# USB_A.net
KiCad netlist of a schematic drawn in Altium Designer
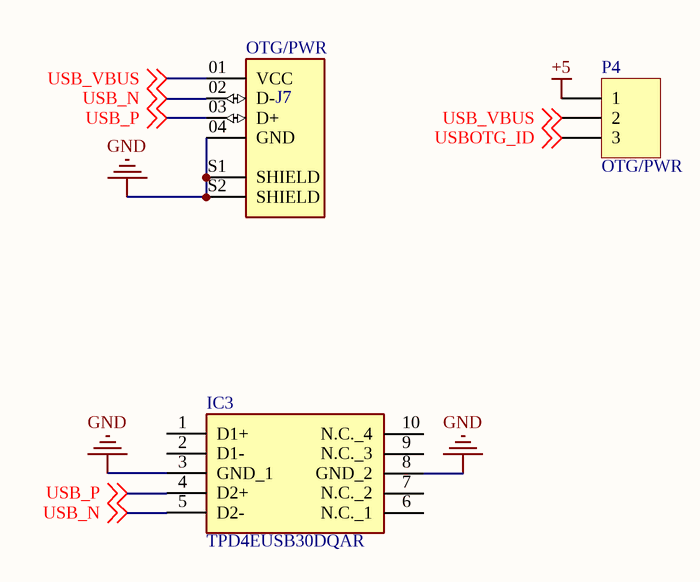
[diagram p0: USB A.SchDoc]

(export (version "E")
  (design (tool "Eeschema 10.0.6"))
  (components
    (comp (ref "IC3")
      (value "TPD4EUSB30DQAR")
      (footprint "SamacSys:DQA(R-PUSON-N10)")
      (description "Integrated Circuit")
      (fields (field (name "MOUSER PART NUMBER") "595-TPD4EUSB30DQAR"))
      (libsource (lib "*") (part "TPD4EUSB30DQAR"))
    )
    (comp (ref "J7")
      (value "OTG/PWR")
      (footprint "SnapEDApcb:SAMTEC_USB-A-S-X-X-SM2")
      (description "USB-A (USB TYPE-A) USB 2.0 Receptacle Connector 4 Position Surface Mount, Right Angle")
      (fields (field (name "MP") "USB-A-S-F-B-SM2") (field (name "MF") "Samtec"))
      (libsource (lib "*") (part "USB-A-S-X-X-SM2"))
    )
    (comp (ref "P4")
      (value "OTG/PWR")
      (footprint "HDR1X3")
      (description "Header, 3-Pin")
      (fields (field (name "PUBLISHER") "Altium Limited"))
      (libsource (lib "Miscellaneous Connectors") (part "Header 3"))
    )
  )
  (nets
    (net (code "1") (name "+5") (class "Default")
      (node (ref "P4") (pin "1") (pinfunction "1_1") (pintype "passive"))
    )
    (net (code "2") (name "GND") (class "Default")
      (node (ref "IC3") (pin "3") (pinfunction "GND_1_3") (pintype "passive"))
      (node (ref "IC3") (pin "8") (pinfunction "GND_2_8") (pintype "passive"))
      (node (ref "J7") (pin "04") (pinfunction "GND_04") (pintype "power_in"))
      (node (ref "J7") (pin "S1") (pinfunction "SHIELD_S1") (pintype "passive"))
      (node (ref "J7") (pin "S2") (pinfunction "SHIELD_S2") (pintype "passive"))
    )
    (net (code "3") (name "USBOTG_ID") (class "Default")
      (node (ref "P4") (pin "3") (pinfunction "3_3") (pintype "passive"))
    )
    (net (code "4") (name "USB_N") (class "Default")
      (node (ref "IC3") (pin "5") (pinfunction "D2-_5") (pintype "passive"))
      (node (ref "J7") (pin "02") (pinfunction "D-_02") (pintype "bidirectional"))
    )
    (net (code "5") (name "USB_P") (class "Default")
      (node (ref "IC3") (pin "4") (pinfunction "D2+_4") (pintype "passive"))
      (node (ref "J7") (pin "03") (pinfunction "D+_03") (pintype "bidirectional"))
    )
    (net (code "6") (name "USB_VBUS") (class "Default")
      (node (ref "J7") (pin "01") (pinfunction "VCC_01") (pintype "power_in"))
      (node (ref "P4") (pin "2") (pinfunction "2_2") (pintype "passive"))
    )
    (net (code "7") (name "unconnected-(IC3-D1+-Pad1)") (class "Default")
      (node (ref "IC3") (pin "1") (pinfunction "D1+_1") (pintype "passive"))
    )
    (net (code "8") (name "unconnected-(IC3-D1--Pad2)") (class "Default")
      (node (ref "IC3") (pin "2") (pinfunction "D1-_2") (pintype "passive"))
    )
    (net (code "9") (name "unconnected-(IC3-N.C._1-Pad6)") (class "Default")
      (node (ref "IC3") (pin "6") (pinfunction "N.C._1_6") (pintype "passive"))
    )
    (net (code "10") (name "unconnected-(IC3-N.C._2-Pad7)") (class "Default")
      (node (ref "IC3") (pin "7") (pinfunction "N.C._2_7") (pintype "passive"))
    )
    (net (code "11") (name "unconnected-(IC3-N.C._3-Pad9)") (class "Default")
      (node (ref "IC3") (pin "9") (pinfunction "N.C._3_9") (pintype "passive"))
    )
    (net (code "12") (name "unconnected-(IC3-N.C._4-Pad10)") (class "Default")
      (node (ref "IC3") (pin "10") (pinfunction "N.C._4_10") (pintype "passive"))
    )
  )
)
